# LeafCanV001.net
KiCad netlist of a schematic drawn in EAGLE
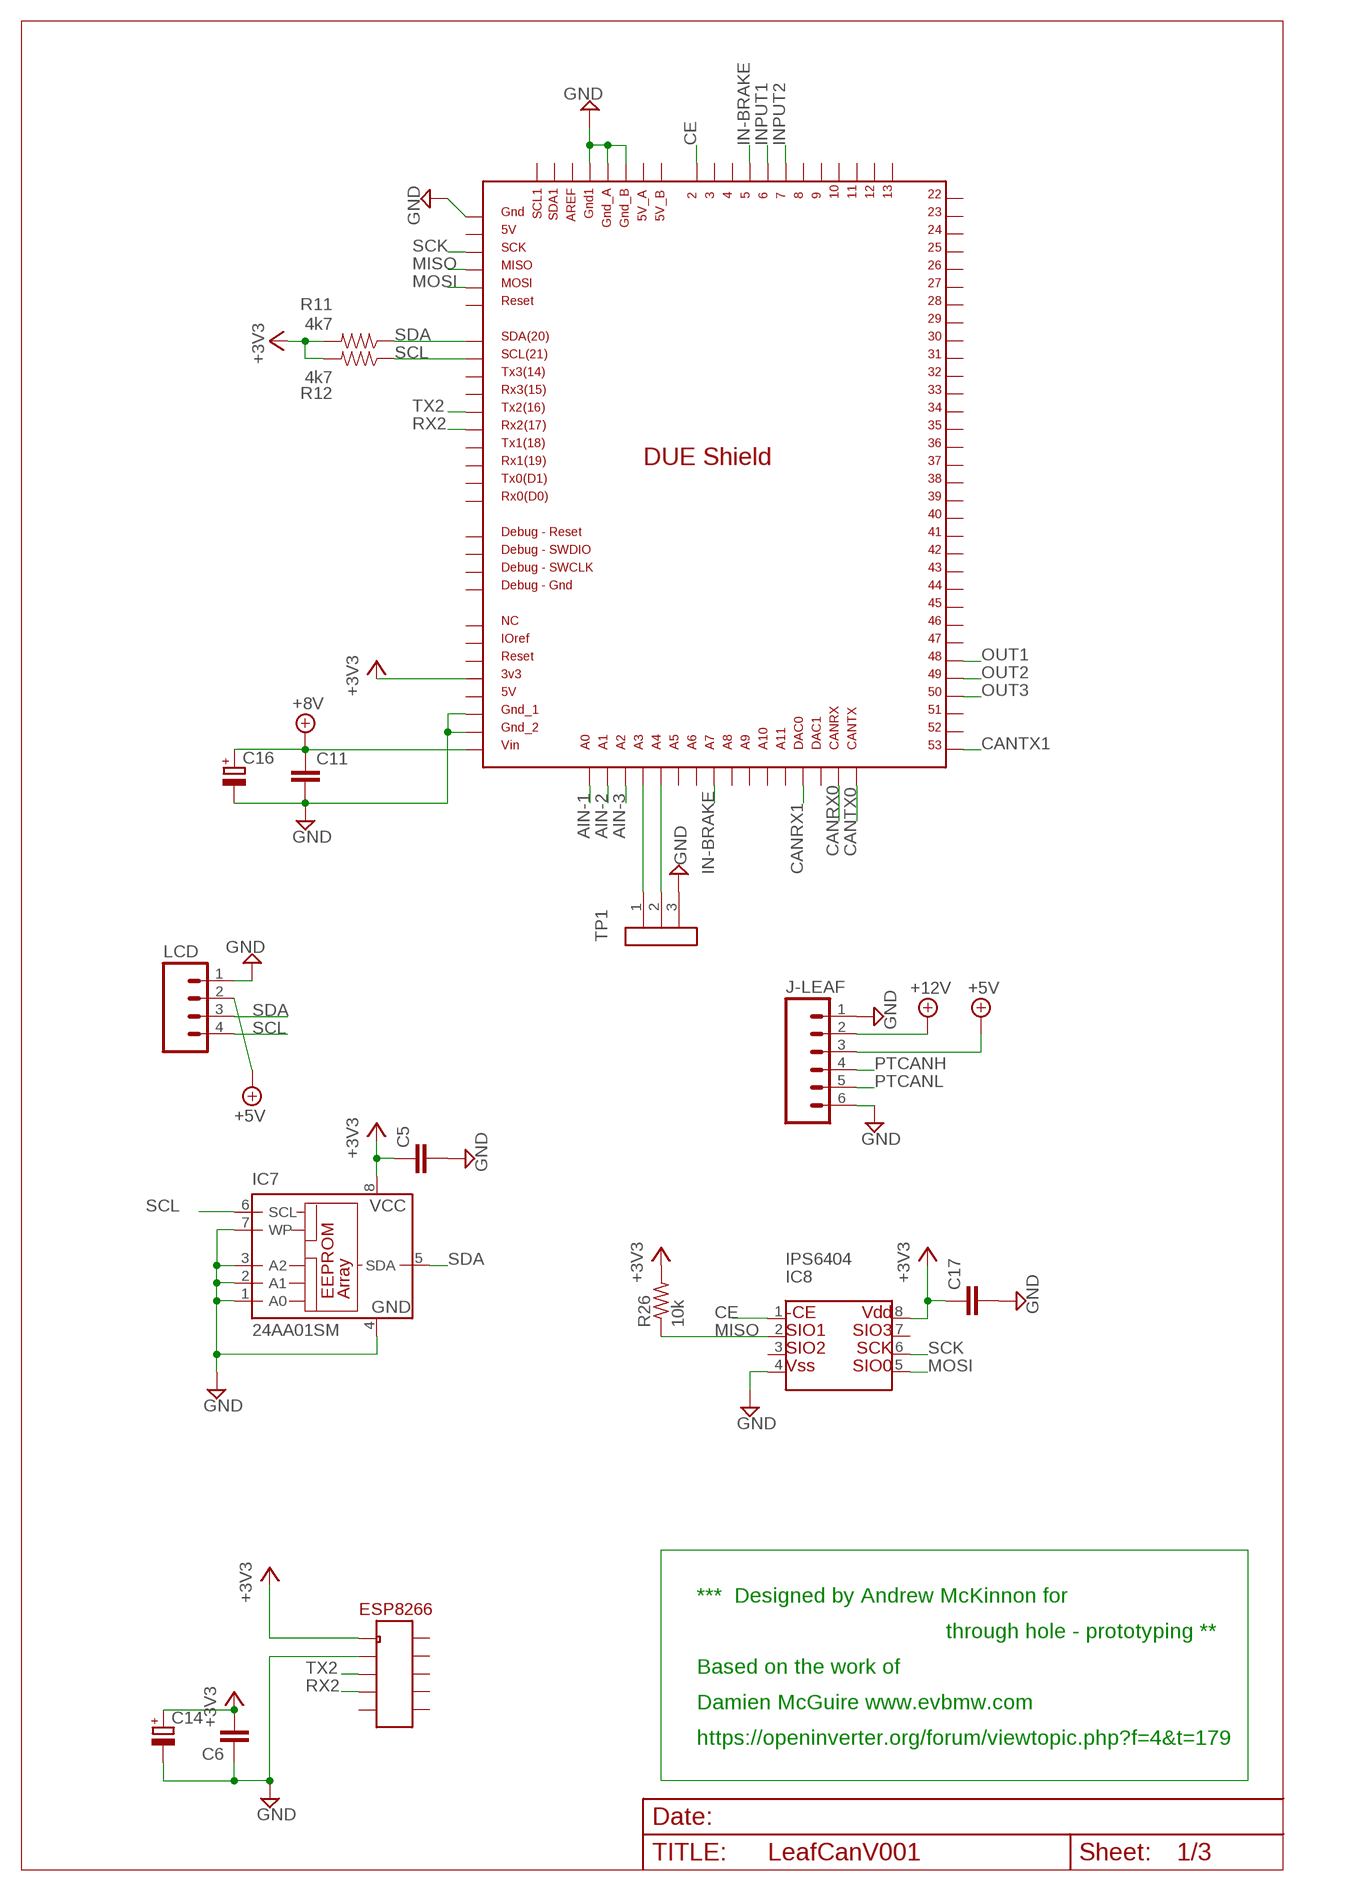
[diagram p0: schematic, sheet 1]
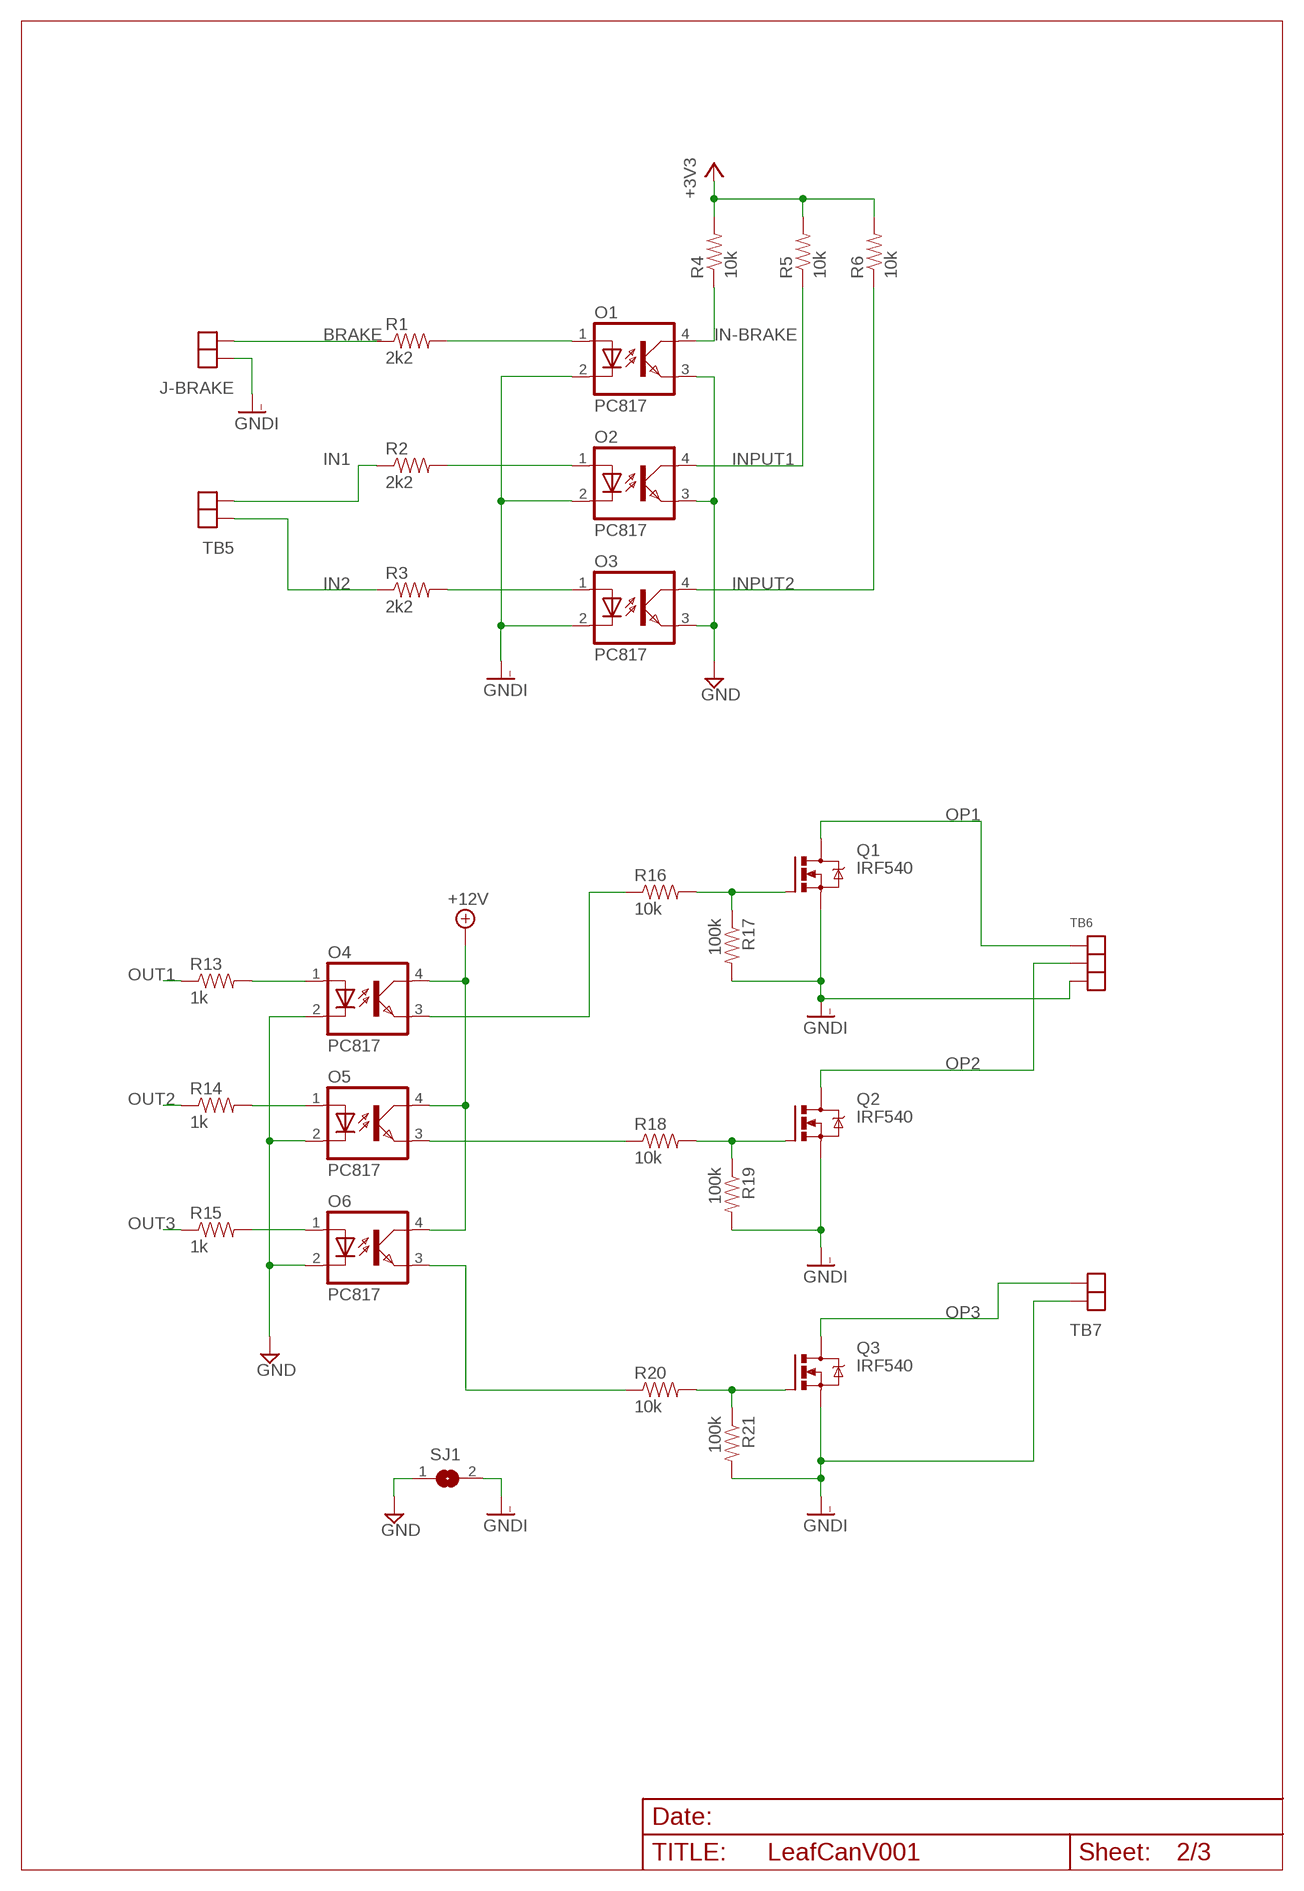
[diagram p1: schematic, sheet 2]
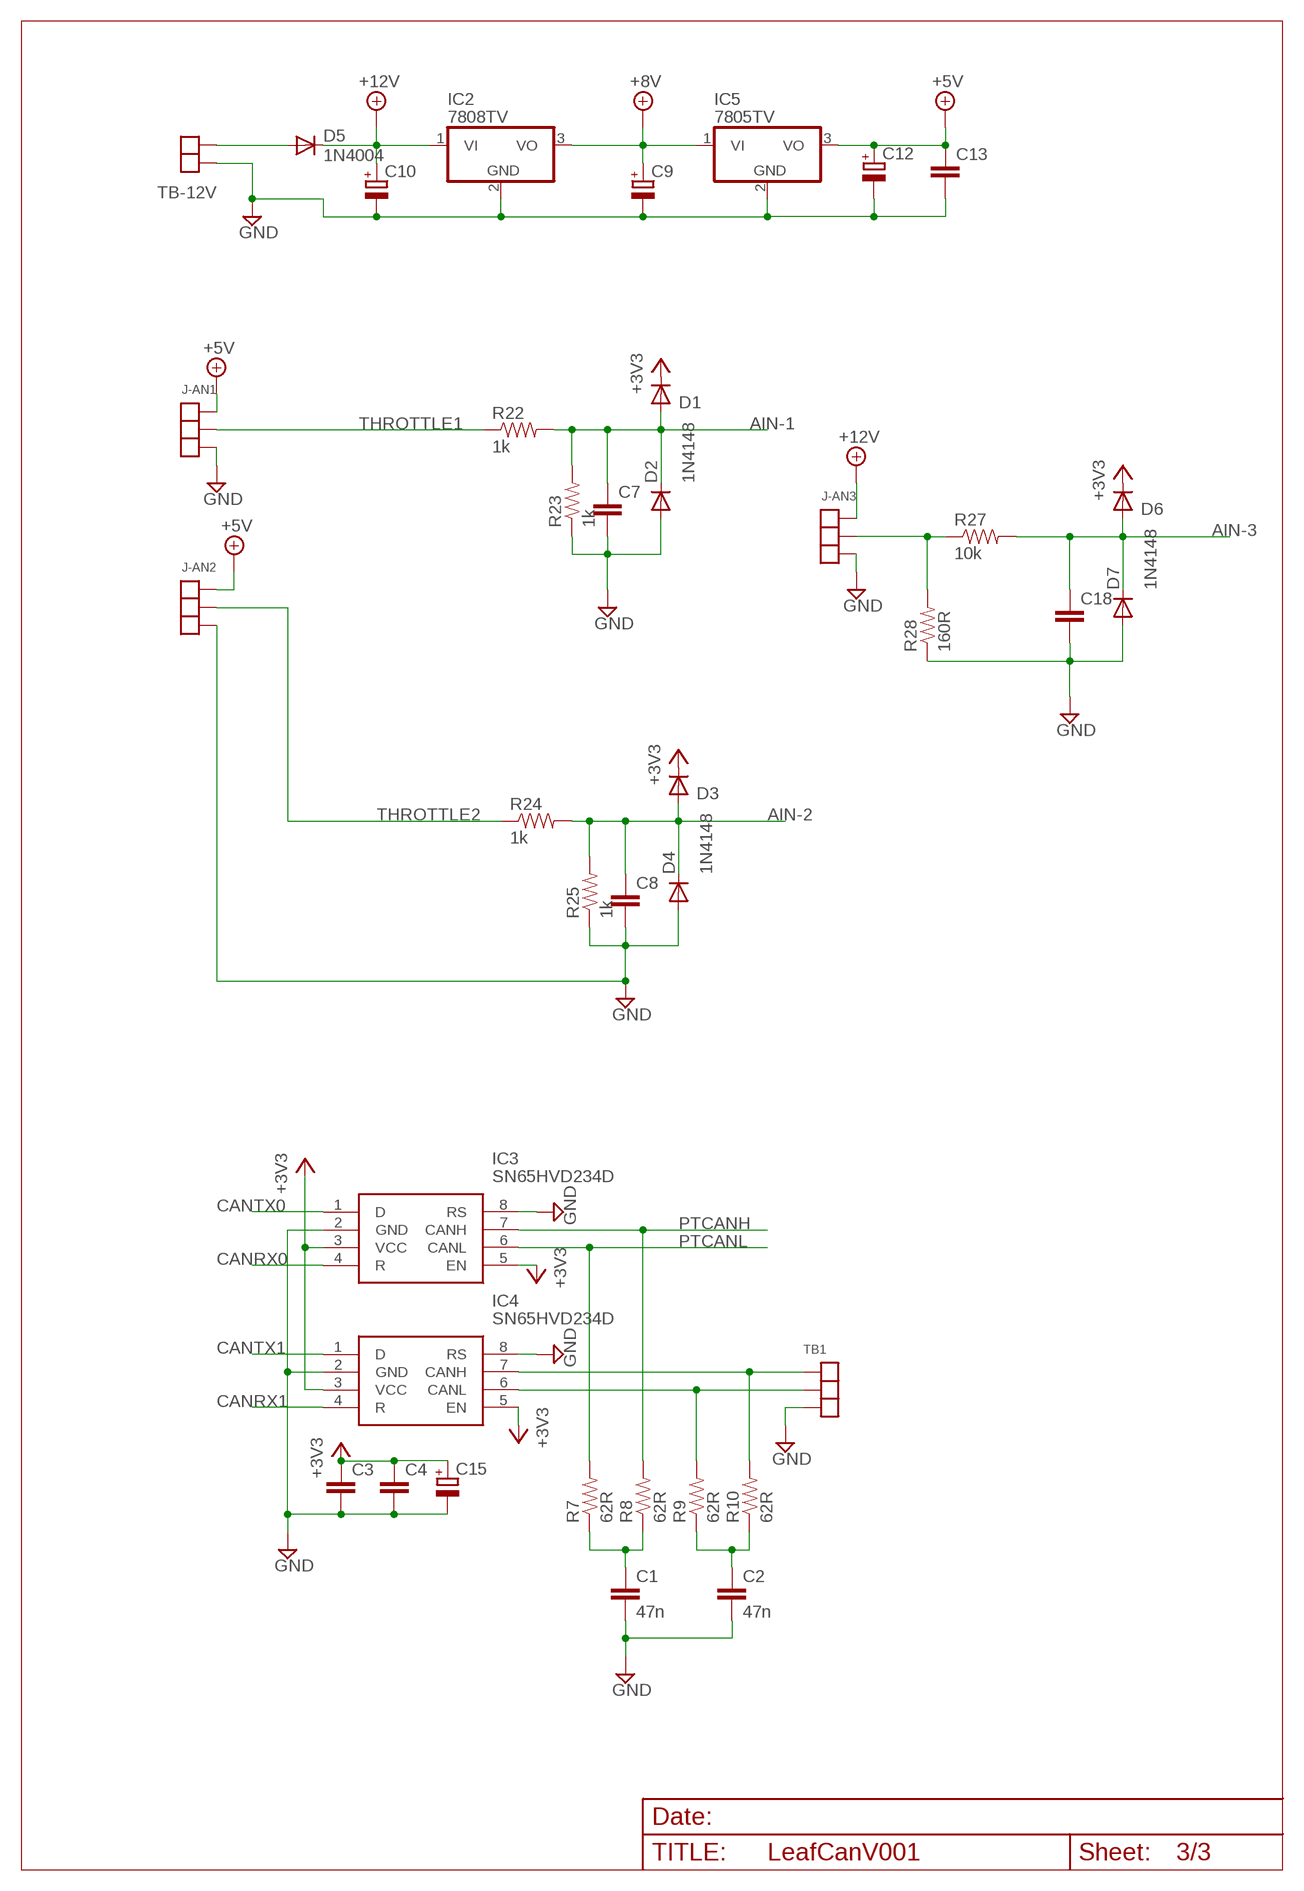
[diagram p2: schematic, sheet 3]

(export (version "E")
  (design (tool "Eeschema 10.0.6"))
  (components
    (comp (ref "C1")
      (value "47n")
      (footprint "eagle-import:C025-030X050")
      (libsource (lib "eagle-import") (part "C-EU025-030X050"))
    )
    (comp (ref "C2")
      (value "47n")
      (footprint "eagle-import:C025-030X050")
      (libsource (lib "eagle-import") (part "C-EU025-030X050"))
    )
    (comp (ref "C3")
      (value "BCAP")
      (footprint "eagle-import:BCAP")
      (libsource (lib "eagle-import") (part "BCAP"))
    )
    (comp (ref "C4")
      (value "BCAP")
      (footprint "eagle-import:BCAP")
      (libsource (lib "eagle-import") (part "BCAP"))
    )
    (comp (ref "C7")
      (value "BCAP")
      (footprint "eagle-import:BCAP")
      (libsource (lib "eagle-import") (part "BCAP"))
    )
    (comp (ref "C8")
      (value "BCAP")
      (footprint "eagle-import:BCAP")
      (libsource (lib "eagle-import") (part "BCAP"))
    )
    (comp (ref "C9")
      (value "C-RB200100")
      (footprint "eagle-import:CPOL-RADIAL-10UF-25V")
      (libsource (lib "eagle-import") (part "C-RB200100"))
    )
    (comp (ref "C10")
      (value "CPOL-EUE7.5-18")
      (footprint "eagle-import:E7,5-18")
      (libsource (lib "eagle-import") (part "CPOL-EUE7.5-18"))
    )
    (comp (ref "C12")
      (value "C-RB200100")
      (footprint "eagle-import:CPOL-RADIAL-10UF-25V")
      (libsource (lib "eagle-import") (part "C-RB200100"))
    )
    (comp (ref "C13")
      (value "BCAP")
      (footprint "eagle-import:BCAP")
      (libsource (lib "eagle-import") (part "BCAP"))
    )
    (comp (ref "C15")
      (value "C-RB200100")
      (footprint "eagle-import:CPOL-RADIAL-10UF-25V")
      (libsource (lib "eagle-import") (part "Andrew Passive_C-RB200100"))
    )
    (comp (ref "C18")
      (value "BCAP")
      (footprint "eagle-import:BCAP")
      (libsource (lib "eagle-import") (part "BCAP"))
    )
    (comp (ref "D1")
      (value "1N4148")
      (footprint "eagle-import:D3")
      (libsource (lib "eagle-import") (part "1N4148DO35-7"))
    )
    (comp (ref "D2")
      (value "1N4148")
      (footprint "eagle-import:D3")
      (libsource (lib "eagle-import") (part "1N4148DO35-7"))
    )
    (comp (ref "D3")
      (value "1N4148")
      (footprint "eagle-import:D3")
      (libsource (lib "eagle-import") (part "1N4148DO35-7"))
    )
    (comp (ref "D4")
      (value "1N4148")
      (footprint "eagle-import:D3")
      (libsource (lib "eagle-import") (part "1N4148DO35-7"))
    )
    (comp (ref "D5")
      (value "1N4004")
      (footprint "eagle-import:DO41-10")
      (libsource (lib "eagle-import") (part "1N4004"))
    )
    (comp (ref "D6")
      (value "1N4148")
      (footprint "eagle-import:D3")
      (libsource (lib "eagle-import") (part "1N4148DO35-7"))
    )
    (comp (ref "D7")
      (value "1N4148")
      (footprint "eagle-import:D3")
      (libsource (lib "eagle-import") (part "1N4148DO35-7"))
    )
    (comp (ref "IC2")
      (value "7808TV")
      (footprint "eagle-import:TO220V")
      (libsource (lib "eagle-import") (part "78TV08"))
    )
    (comp (ref "IC3")
      (value "SN65HVD234D")
      (footprint "eagle-import:SOIC127P600X175-8N")
      (fields
        (field (name "MOUSER_PART_NUMBER") "595-SN65HVD234D")
        (field (name "RS_PART_NUMBER") "6624315P")
      )
      (libsource (lib "eagle-import") (part "SN65HVD234D"))
    )
    (comp (ref "IC4")
      (value "SN65HVD234D")
      (footprint "eagle-import:SOIC127P600X175-8N")
      (fields
        (field (name "MOUSER_PART_NUMBER") "595-SN65HVD234D")
        (field (name "RS_PART_NUMBER") "6624315P")
      )
      (libsource (lib "eagle-import") (part "SN65HVD234D"))
    )
    (comp (ref "IC5")
      (value "7805TV")
      (footprint "eagle-import:TO220V")
      (libsource (lib "eagle-import") (part "78TV05"))
    )
    (comp (ref "J-AN1")
      (value "TB3381V")
      (footprint "eagle-import:TB-KF2EDG381-3-V")
      (libsource (lib "eagle-import") (part "TB3381V"))
    )
    (comp (ref "J-AN2")
      (value "TB3381V")
      (footprint "eagle-import:TB-KF2EDG381-3-V")
      (libsource (lib "eagle-import") (part "TB3381V"))
    )
    (comp (ref "J-AN3")
      (value "TB3381V")
      (footprint "eagle-import:TB-KF2EDG381-3-V")
      (libsource (lib "eagle-import") (part "TB3381V"))
    )
    (comp (ref "R7")
      (value "62R")
      (footprint "eagle-import:AXIAL-0.4")
      (libsource (lib "eagle-import") (part "R4"))
    )
    (comp (ref "R8")
      (value "62R")
      (footprint "eagle-import:AXIAL-0.4")
      (libsource (lib "eagle-import") (part "R4"))
    )
    (comp (ref "R9")
      (value "62R")
      (footprint "eagle-import:AXIAL-0.4")
      (libsource (lib "eagle-import") (part "R4"))
    )
    (comp (ref "R10")
      (value "62R")
      (footprint "eagle-import:AXIAL-0.4")
      (libsource (lib "eagle-import") (part "R4"))
    )
    (comp (ref "R22")
      (value "1k")
      (footprint "eagle-import:AXIAL-0.4")
      (libsource (lib "eagle-import") (part "R4"))
    )
    (comp (ref "R23")
      (value "1k")
      (footprint "eagle-import:AXIAL-0.4")
      (libsource (lib "eagle-import") (part "R4"))
    )
    (comp (ref "R24")
      (value "1k")
      (footprint "eagle-import:AXIAL-0.4")
      (libsource (lib "eagle-import") (part "R4"))
    )
    (comp (ref "R25")
      (value "1k")
      (footprint "eagle-import:AXIAL-0.4")
      (libsource (lib "eagle-import") (part "R4"))
    )
    (comp (ref "R27")
      (value "10k")
      (footprint "eagle-import:AXIAL-0.4")
      (libsource (lib "eagle-import") (part "R4"))
    )
    (comp (ref "R28")
      (value "160R")
      (footprint "eagle-import:AXIAL-0.4")
      (libsource (lib "eagle-import") (part "R4"))
    )
    (comp (ref "TB-12V")
      (value "TB2381")
      (footprint "eagle-import:TB-KF2EDG381-2P")
      (libsource (lib "eagle-import") (part "TB2381"))
    )
    (comp (ref "TB1")
      (value "TB3381V")
      (footprint "eagle-import:TB-KF2EDG381-3-V")
      (libsource (lib "eagle-import") (part "TB3381V"))
    )
    (comp (ref "J-BRAKE")
      (value "TB2381")
      (footprint "eagle-import:TB-KF2EDG381-2P")
      (libsource (lib "eagle-import") (part "TB2381"))
    )
    (comp (ref "O1")
      (value "PC817")
      (footprint "eagle-import:DIL04")
      (fields (field (name "MPN") "PC817X4J000F"))
      (libsource (lib "eagle-import") (part "PC817"))
    )
    (comp (ref "O2")
      (value "PC817")
      (footprint "eagle-import:DIL04")
      (fields (field (name "MPN") "PC817X4J000F"))
      (libsource (lib "eagle-import") (part "PC817"))
    )
    (comp (ref "O3")
      (value "PC817")
      (footprint "eagle-import:DIL04")
      (fields (field (name "MPN") "PC817X4J000F"))
      (libsource (lib "eagle-import") (part "PC817"))
    )
    (comp (ref "O4")
      (value "PC817")
      (footprint "eagle-import:DIL04")
      (fields (field (name "MPN") "PC817X4J000F"))
      (libsource (lib "eagle-import") (part "PC817"))
    )
    (comp (ref "O5")
      (value "PC817")
      (footprint "eagle-import:DIL04")
      (fields (field (name "MPN") "PC817X4J000F"))
      (libsource (lib "eagle-import") (part "PC817"))
    )
    (comp (ref "O6")
      (value "PC817")
      (footprint "eagle-import:DIL04")
      (fields (field (name "MPN") "PC817X4J000F"))
      (libsource (lib "eagle-import") (part "PC817"))
    )
    (comp (ref "Q1")
      (value "IRF540")
      (footprint "eagle-import:TO220BV")
      (libsource (lib "eagle-import") (part "IRF540"))
    )
    (comp (ref "Q2")
      (value "IRF540")
      (footprint "eagle-import:TO220BV")
      (libsource (lib "eagle-import") (part "IRF540"))
    )
    (comp (ref "Q3")
      (value "IRF540")
      (footprint "eagle-import:TO220BV")
      (libsource (lib "eagle-import") (part "IRF540"))
    )
    (comp (ref "R1")
      (value "2k2")
      (footprint "eagle-import:AXIAL-0.4")
      (libsource (lib "eagle-import") (part "R4"))
    )
    (comp (ref "R2")
      (value "2k2")
      (footprint "eagle-import:AXIAL-0.4")
      (libsource (lib "eagle-import") (part "R4"))
    )
    (comp (ref "R3")
      (value "2k2")
      (footprint "eagle-import:AXIAL-0.4")
      (libsource (lib "eagle-import") (part "R4"))
    )
    (comp (ref "R4")
      (value "10k")
      (footprint "eagle-import:AXIAL-0.4")
      (libsource (lib "eagle-import") (part "R4"))
    )
    (comp (ref "R5")
      (value "10k")
      (footprint "eagle-import:AXIAL-0.4")
      (libsource (lib "eagle-import") (part "R4"))
    )
    (comp (ref "R6")
      (value "10k")
      (footprint "eagle-import:AXIAL-0.4")
      (libsource (lib "eagle-import") (part "R4"))
    )
    (comp (ref "R13")
      (value "1k")
      (footprint "eagle-import:AXIAL-0.4")
      (libsource (lib "eagle-import") (part "R4"))
    )
    (comp (ref "R14")
      (value "1k")
      (footprint "eagle-import:AXIAL-0.4")
      (libsource (lib "eagle-import") (part "R4"))
    )
    (comp (ref "R15")
      (value "1k")
      (footprint "eagle-import:AXIAL-0.4")
      (libsource (lib "eagle-import") (part "R4"))
    )
    (comp (ref "R16")
      (value "10k")
      (footprint "eagle-import:AXIAL-0.4")
      (libsource (lib "eagle-import") (part "R4"))
    )
    (comp (ref "R17")
      (value "100k")
      (footprint "eagle-import:AXIAL-0.4")
      (libsource (lib "eagle-import") (part "R4"))
    )
    (comp (ref "R18")
      (value "10k")
      (footprint "eagle-import:AXIAL-0.4")
      (libsource (lib "eagle-import") (part "R4"))
    )
    (comp (ref "R19")
      (value "100k")
      (footprint "eagle-import:AXIAL-0.4")
      (libsource (lib "eagle-import") (part "R4"))
    )
    (comp (ref "R20")
      (value "10k")
      (footprint "eagle-import:AXIAL-0.4")
      (libsource (lib "eagle-import") (part "R4"))
    )
    (comp (ref "R21")
      (value "100k")
      (footprint "eagle-import:AXIAL-0.4")
      (libsource (lib "eagle-import") (part "R4"))
    )
    (comp (ref "SJ1") (value "SJ") (footprint "eagle-import:SJ") (libsource (lib "eagle-import") (part "SJ")))
    (comp (ref "TB5")
      (value "TB2381")
      (footprint "eagle-import:TB-KF2EDG381-2P")
      (libsource (lib "eagle-import") (part "TB2381"))
    )
    (comp (ref "TB6")
      (value "TB3381")
      (footprint "eagle-import:TB-KF2EDG381-3P")
      (libsource (lib "eagle-import") (part "TB3381"))
    )
    (comp (ref "TB7")
      (value "TB2381")
      (footprint "eagle-import:TB-KF2EDG381-2P")
      (libsource (lib "eagle-import") (part "TB2381"))
    )
    (comp (ref "C5")
      (value "BCAP")
      (footprint "eagle-import:BCAP")
      (libsource (lib "eagle-import") (part "BCAP"))
    )
    (comp (ref "C6")
      (value "BCAP")
      (footprint "eagle-import:BCAP")
      (libsource (lib "eagle-import") (part "BCAP"))
    )
    (comp (ref "C11")
      (value "BCAP")
      (footprint "eagle-import:BCAP")
      (libsource (lib "eagle-import") (part "BCAP"))
    )
    (comp (ref "C14")
      (value "C-RB200100")
      (footprint "eagle-import:CPOL-RADIAL-10UF-25V")
      (libsource (lib "eagle-import") (part "Andrew Passive_C-RB200100"))
    )
    (comp (ref "C16")
      (value "C-RB200100")
      (footprint "eagle-import:CPOL-RADIAL-10UF-25V")
      (libsource (lib "eagle-import") (part "Andrew Passive_C-RB200100"))
    )
    (comp (ref "C17")
      (value "BCAP")
      (footprint "eagle-import:BCAP")
      (libsource (lib "eagle-import") (part "BCAP"))
    )
    (comp (ref "ESP8266")
      (value "IDC10")
      (footprint "eagle-import:IDC10-SMALL")
      (libsource (lib "eagle-import") (part "IDC10"))
    )
    (comp (ref "IC1")
      (value "DUE(NORMAL)")
      (footprint "eagle-import:DUE(NORMAL)")
      (libsource (lib "eagle-import") (part "DUE(NORMAL)"))
    )
    (comp (ref "IC7")
      (value "24AA01SM")
      (footprint "eagle-import:SO-08M")
      (fields (field (name "MF") "MICROCHIP") (field (name "MPN") "24AA01-I/SN"))
      (libsource (lib "eagle-import") (part "24SMAA01"))
    )
    (comp (ref "IC8")
      (value "IPS6404")
      (footprint "eagle-import:SO-08")
      (libsource (lib "eagle-import") (part "IPS6404"))
    )
    (comp (ref "J-LEAF")
      (value "MO6POL")
      (footprint "eagle-import:MOLEX-6")
      (libsource (lib "eagle-import") (part "MO6POL"))
    )
    (comp (ref "LCD")
      (value "MO4POL")
      (footprint "eagle-import:MOLEX-4")
      (libsource (lib "eagle-import") (part "MO4POL"))
    )
    (comp (ref "R11")
      (value "4k7")
      (footprint "eagle-import:AXIAL-0.4")
      (libsource (lib "eagle-import") (part "R4"))
    )
    (comp (ref "R12")
      (value "4k7")
      (footprint "eagle-import:AXIAL-0.4")
      (libsource (lib "eagle-import") (part "R4"))
    )
    (comp (ref "R26")
      (value "10k")
      (footprint "eagle-import:R1206")
      (libsource (lib "eagle-import") (part "R-US_R1206"))
    )
    (comp (ref "TP1")
      (value "SIL3")
      (footprint "eagle-import:SIL3")
      (libsource (lib "eagle-import") (part "SIL3"))
    )
  )
  (nets
    (net (code "1") (name "+3V3") (class "Default")
      (node (ref "C14") (pin "1") (pinfunction "+_1") (pintype "passive"))
      (node (ref "C15") (pin "1") (pinfunction "+_1") (pintype "passive"))
      (node (ref "C17") (pin "1") (pinfunction "1_1") (pintype "passive"))
      (node (ref "C3") (pin "1") (pinfunction "1_1") (pintype "passive"))
      (node (ref "C4") (pin "1") (pinfunction "1_1") (pintype "passive"))
      (node (ref "C5") (pin "1") (pinfunction "1_1") (pintype "passive"))
      (node (ref "C6") (pin "2") (pinfunction "2_2") (pintype "passive"))
      (node (ref "D1") (pin "C") (pinfunction "C_C") (pintype "passive"))
      (node (ref "D3") (pin "C") (pinfunction "C_C") (pintype "passive"))
      (node (ref "D6") (pin "C") (pinfunction "C_C") (pintype "passive"))
      (node (ref "ESP8266") (pin "1") (pinfunction "1_1") (pintype "bidirectional"))
      (node (ref "IC1") (pin "3V3") (pinfunction "3V3_3V3") (pintype "bidirectional"))
      (node (ref "IC3") (pin "3") (pinfunction "VCC_3") (pintype "bidirectional"))
      (node (ref "IC3") (pin "5") (pinfunction "EN_5") (pintype "bidirectional"))
      (node (ref "IC4") (pin "3") (pinfunction "VCC_3") (pintype "bidirectional"))
      (node (ref "IC4") (pin "5") (pinfunction "EN_5") (pintype "bidirectional"))
      (node (ref "IC7") (pin "8") (pinfunction "VCC_8") (pintype "power_in"))
      (node (ref "IC8") (pin "8") (pinfunction "P$8_8") (pintype "bidirectional"))
      (node (ref "R11") (pin "P$2") (pinfunction "2_P$2") (pintype "passive"))
      (node (ref "R12") (pin "P$2") (pinfunction "2_P$2") (pintype "passive"))
      (node (ref "R26") (pin "2") (pinfunction "2_2") (pintype "passive"))
      (node (ref "R4") (pin "P$2") (pinfunction "2_P$2") (pintype "passive"))
      (node (ref "R5") (pin "P$2") (pinfunction "2_P$2") (pintype "passive"))
      (node (ref "R6") (pin "P$2") (pinfunction "2_P$2") (pintype "passive"))
    )
    (net (code "2") (name "+5V") (class "Default")
      (node (ref "C12") (pin "1") (pinfunction "+_1") (pintype "passive"))
      (node (ref "C13") (pin "1") (pinfunction "1_1") (pintype "passive"))
      (node (ref "IC5") (pin "3") (pinfunction "VO_3") (pintype "passive"))
      (node (ref "J-AN1") (pin "1") (pinfunction "1_1") (pintype "bidirectional"))
      (node (ref "J-AN2") (pin "1") (pinfunction "1_1") (pintype "bidirectional"))
      (node (ref "J-LEAF") (pin "3") (pinfunction "3_3") (pintype "passive"))
      (node (ref "LCD") (pin "2") (pinfunction "2_2") (pintype "passive"))
    )
    (net (code "3") (name "+8V") (class "Default")
      (node (ref "C11") (pin "1") (pinfunction "1_1") (pintype "passive"))
      (node (ref "C16") (pin "1") (pinfunction "+_1") (pintype "passive"))
      (node (ref "C9") (pin "1") (pinfunction "+_1") (pintype "passive"))
      (node (ref "IC1") (pin "VIN") (pinfunction "VIN_VIN") (pintype "bidirectional"))
      (node (ref "IC2") (pin "3") (pinfunction "VO_3") (pintype "passive"))
      (node (ref "IC5") (pin "1") (pinfunction "VI_1") (pintype "input"))
    )
    (net (code "4") (name "+12V") (class "Default")
      (node (ref "C10") (pin "+") (pinfunction "+_+") (pintype "passive"))
      (node (ref "D5") (pin "C") (pinfunction "C_C") (pintype "passive"))
      (node (ref "IC2") (pin "1") (pinfunction "VI_1") (pintype "input"))
      (node (ref "J-AN3") (pin "1") (pinfunction "1_1") (pintype "bidirectional"))
      (node (ref "J-LEAF") (pin "2") (pinfunction "2_2") (pintype "passive"))
      (node (ref "O4") (pin "4") (pinfunction "COL_4") (pintype "passive"))
      (node (ref "O5") (pin "4") (pinfunction "COL_4") (pintype "passive"))
      (node (ref "O6") (pin "4") (pinfunction "COL_4") (pintype "passive"))
    )
    (net (code "5") (name "AIN-1") (class "Default")
      (node (ref "C7") (pin "1") (pinfunction "1_1") (pintype "passive"))
      (node (ref "D1") (pin "A") (pinfunction "A_A") (pintype "passive"))
      (node (ref "D2") (pin "C") (pinfunction "C_C") (pintype "passive"))
      (node (ref "IC1") (pin "A0") (pinfunction "A0_A0") (pintype "bidirectional"))
      (node (ref "R22") (pin "P$2") (pinfunction "2_P$2") (pintype "passive"))
      (node (ref "R23") (pin "P$2") (pinfunction "2_P$2") (pintype "passive"))
    )
    (net (code "6") (name "AIN-2") (class "Default")
      (node (ref "C8") (pin "1") (pinfunction "1_1") (pintype "passive"))
      (node (ref "D3") (pin "A") (pinfunction "A_A") (pintype "passive"))
      (node (ref "D4") (pin "C") (pinfunction "C_C") (pintype "passive"))
      (node (ref "IC1") (pin "A1") (pinfunction "A1_A1") (pintype "bidirectional"))
      (node (ref "R24") (pin "P$2") (pinfunction "2_P$2") (pintype "passive"))
      (node (ref "R25") (pin "P$2") (pinfunction "2_P$2") (pintype "passive"))
    )
    (net (code "7") (name "AIN-3") (class "Default")
      (node (ref "C18") (pin "1") (pinfunction "1_1") (pintype "passive"))
      (node (ref "D6") (pin "A") (pinfunction "A_A") (pintype "passive"))
      (node (ref "D7") (pin "C") (pinfunction "C_C") (pintype "passive"))
      (node (ref "IC1") (pin "A2") (pinfunction "A2_A2") (pintype "bidirectional"))
      (node (ref "R27") (pin "P$2") (pinfunction "2_P$2") (pintype "passive"))
    )
    (net (code "8") (name "BRAKE") (class "Default")
      (node (ref "J-BRAKE") (pin "1") (pinfunction "1_1") (pintype "bidirectional"))
      (node (ref "R1") (pin "P$1") (pinfunction "1_P$1") (pintype "passive"))
    )
    (net (code "9") (name "CANRX0") (class "Default")
      (node (ref "IC1") (pin "CANRX") (pinfunction "CANRX_CANRX") (pintype "bidirectional"))
      (node (ref "IC3") (pin "4") (pinfunction "R_4") (pintype "bidirectional"))
    )
    (net (code "10") (name "CANRX1") (class "Default")
      (node (ref "IC1") (pin "DAC0") (pinfunction "DAC0_DAC0") (pintype "bidirectional"))
      (node (ref "IC4") (pin "4") (pinfunction "R_4") (pintype "bidirectional"))
    )
    (net (code "11") (name "CANTX0") (class "Default")
      (node (ref "IC1") (pin "CANTX") (pinfunction "CANTX_CANTX") (pintype "bidirectional"))
      (node (ref "IC3") (pin "1") (pinfunction "D_1") (pintype "bidirectional"))
    )
    (net (code "12") (name "CANTX1") (class "Default")
      (node (ref "IC1") (pin "53") (pinfunction "53_53") (pintype "bidirectional"))
      (node (ref "IC4") (pin "1") (pinfunction "D_1") (pintype "bidirectional"))
    )
    (net (code "13") (name "CE") (class "Default")
      (node (ref "IC1") (pin "2") (pinfunction "2_2") (pintype "bidirectional"))
      (node (ref "IC8") (pin "1") (pinfunction "P$1_1") (pintype "bidirectional"))
    )
    (net (code "14") (name "GND") (class "Default")
      (node (ref "C1") (pin "2") (pinfunction "2_2") (pintype "passive"))
      (node (ref "C10") (pin "-") (pinfunction "-_-") (pintype "passive"))
      (node (ref "C11") (pin "2") (pinfunction "2_2") (pintype "passive"))
      (node (ref "C12") (pin "2") (pinfunction "-_2") (pintype "passive"))
      (node (ref "C13") (pin "2") (pinfunction "2_2") (pintype "passive"))
      (node (ref "C14") (pin "2") (pinfunction "-_2") (pintype "passive"))
      (node (ref "C15") (pin "2") (pinfunction "-_2") (pintype "passive"))
      (node (ref "C16") (pin "2") (pinfunction "-_2") (pintype "passive"))
      (node (ref "C17") (pin "2") (pinfunction "2_2") (pintype "passive"))
      (node (ref "C18") (pin "2") (pinfunction "2_2") (pintype "passive"))
      (node (ref "C2") (pin "2") (pinfunction "2_2") (pintype "passive"))
      (node (ref "C3") (pin "2") (pinfunction "2_2") (pintype "passive"))
      (node (ref "C4") (pin "2") (pinfunction "2_2") (pintype "passive"))
      (node (ref "C5") (pin "2") (pinfunction "2_2") (pintype "passive"))
      (node (ref "C6") (pin "1") (pinfunction "1_1") (pintype "passive"))
      (node (ref "C7") (pin "2") (pinfunction "2_2") (pintype "passive"))
      (node (ref "C8") (pin "2") (pinfunction "2_2") (pintype "passive"))
      (node (ref "C9") (pin "2") (pinfunction "-_2") (pintype "passive"))
      (node (ref "D2") (pin "A") (pinfunction "A_A") (pintype "passive"))
      (node (ref "D4") (pin "A") (pinfunction "A_A") (pintype "passive"))
      (node (ref "D7") (pin "A") (pinfunction "A_A") (pintype "passive"))
      (node (ref "ESP8266") (pin "3") (pinfunction "3_3") (pintype "bidirectional"))
      (node (ref "IC1") (pin "5V_ICSP") (pinfunction "5V_ICSP_5V_ICSP") (pintype "bidirectional"))
      (node (ref "IC1") (pin "GND1") (pinfunction "GND1_GND1") (pintype "bidirectional"))
      (node (ref "IC1") (pin "GND_1") (pinfunction "GND_1_GND_1") (pintype "bidirectional"))
      (node (ref "IC1") (pin "GND_2") (pinfunction "GND_2_GND_2") (pintype "bidirectional"))
      (node (ref "IC1") (pin "GND_A") (pinfunction "GND_A_GND_A") (pintype "bidirectional"))
      (node (ref "IC1") (pin "GND_B") (pinfunction "GND_B_GND_B") (pintype "bidirectional"))
      (node (ref "IC2") (pin "2") (pinfunction "GND_2") (pintype "passive"))
      (node (ref "IC3") (pin "2") (pinfunction "GND_2") (pintype "bidirectional"))
      (node (ref "IC3") (pin "8") (pinfunction "RS_8") (pintype "bidirectional"))
      (node (ref "IC4") (pin "2") (pinfunction "GND_2") (pintype "bidirectional"))
      (node (ref "IC4") (pin "8") (pinfunction "RS_8") (pintype "bidirectional"))
      (node (ref "IC5") (pin "2") (pinfunction "GND_2") (pintype "passive"))
      (node (ref "IC7") (pin "1") (pinfunction "A0_1") (pintype "input"))
      (node (ref "IC7") (pin "2") (pinfunction "A1_2") (pintype "input"))
      (node (ref "IC7") (pin "3") (pinfunction "A2_3") (pintype "input"))
      (node (ref "IC7") (pin "4") (pinfunction "GND_4") (pintype "power_in"))
      (node (ref "IC7") (pin "7") (pinfunction "WP_7") (pintype "input"))
      (node (ref "IC8") (pin "4") (pinfunction "P$4_4") (pintype "bidirectional"))
      (node (ref "J-AN1") (pin "3") (pinfunction "3_3") (pintype "bidirectional"))
      (node (ref "J-AN2") (pin "3") (pinfunction "3_3") (pintype "bidirectional"))
      (node (ref "J-AN3") (pin "3") (pinfunction "3_3") (pintype "bidirectional"))
      (node (ref "J-LEAF") (pin "1") (pinfunction "1_1") (pintype "passive"))
      (node (ref "J-LEAF") (pin "6") (pinfunction "6_6") (pintype "passive"))
      (node (ref "LCD") (pin "1") (pinfunction "1_1") (pintype "passive"))
      (node (ref "O1") (pin "3") (pinfunction "EMIT_3") (pintype "passive"))
      (node (ref "O2") (pin "3") (pinfunction "EMIT_3") (pintype "passive"))
      (node (ref "O3") (pin "3") (pinfunction "EMIT_3") (pintype "passive"))
      (node (ref "O4") (pin "2") (pinfunction "C_2") (pintype "passive"))
      (node (ref "O5") (pin "2") (pinfunction "C_2") (pintype "passive"))
      (node (ref "O6") (pin "2") (pinfunction "C_2") (pintype "passive"))
      (node (ref "R23") (pin "P$1") (pinfunction "1_P$1") (pintype "passive"))
      (node (ref "R25") (pin "P$1") (pinfunction "1_P$1") (pintype "passive"))
      (node (ref "R28") (pin "P$1") (pinfunction "1_P$1") (pintype "passive"))
      (node (ref "SJ1") (pin "1") (pinfunction "1_1") (pintype "passive"))
      (node (ref "TB-12V") (pin "2") (pinfunction "2_2") (pintype "bidirectional"))
      (node (ref "TB1") (pin "3") (pinfunction "3_3") (pintype "bidirectional"))
      (node (ref "TP1") (pin "3") (pinfunction "P$3_3") (pintype "bidirectional"))
    )
    (net (code "15") (name "GNDI") (class "Default")
      (node (ref "J-BRAKE") (pin "2") (pinfunction "2_2") (pintype "bidirectional"))
      (node (ref "O1") (pin "2") (pinfunction "C_2") (pintype "passive"))
      (node (ref "O2") (pin "2") (pinfunction "C_2") (pintype "passive"))
      (node (ref "O3") (pin "2") (pinfunction "C_2") (pintype "passive"))
      (node (ref "Q1") (pin "S") (pinfunction "S_S") (pintype "passive"))
      (node (ref "Q2") (pin "S") (pinfunction "S_S") (pintype "passive"))
      (node (ref "Q3") (pin "S") (pinfunction "S_S") (pintype "passive"))
      (node (ref "R17") (pin "P$2") (pinfunction "2_P$2") (pintype "passive"))
      (node (ref "R19") (pin "P$2") (pinfunction "2_P$2") (pintype "passive"))
      (node (ref "R21") (pin "P$2") (pinfunction "2_P$2") (pintype "passive"))
      (node (ref "SJ1") (pin "2") (pinfunction "2_2") (pintype "passive"))
      (node (ref "TB6") (pin "3") (pinfunction "3_3") (pintype "bidirectional"))
      (node (ref "TB7") (pin "2") (pinfunction "2_2") (pintype "bidirectional"))
    )
    (net (code "16") (name "IN-BRAKE") (class "Default")
      (node (ref "IC1") (pin "5") (pinfunction "5_5") (pintype "bidirectional"))
      (node (ref "IC1") (pin "A7") (pinfunction "A7_A7") (pintype "bidirectional"))
      (node (ref "O1") (pin "4") (pinfunction "COL_4") (pintype "passive"))
      (node (ref "R4") (pin "P$1") (pinfunction "1_P$1") (pintype "passive"))
    )
    (net (code "17") (name "IN1") (class "Default")
      (node (ref "R2") (pin "P$1") (pinfunction "1_P$1") (pintype "passive"))
      (node (ref "TB5") (pin "1") (pinfunction "1_1") (pintype "bidirectional"))
    )
    (net (code "18") (name "IN2") (class "Default")
      (node (ref "R3") (pin "P$1") (pinfunction "1_P$1") (pintype "passive"))
      (node (ref "TB5") (pin "2") (pinfunction "2_2") (pintype "bidirectional"))
    )
    (net (code "19") (name "INPUT1") (class "Default")
      (node (ref "IC1") (pin "6") (pinfunction "6_6") (pintype "bidirectional"))
      (node (ref "O2") (pin "4") (pinfunction "COL_4") (pintype "passive"))
      (node (ref "R5") (pin "P$1") (pinfunction "1_P$1") (pintype "passive"))
    )
    (net (code "20") (name "INPUT2") (class "Default")
      (node (ref "IC1") (pin "7") (pinfunction "7_7") (pintype "bidirectional"))
      (node (ref "O3") (pin "4") (pinfunction "COL_4") (pintype "passive"))
      (node (ref "R6") (pin "P$1") (pinfunction "1_P$1") (pintype "passive"))
    )
    (net (code "21") (name "MISO") (class "Default")
      (node (ref "IC1") (pin "MISO_ICSP") (pinfunction "MISO_ICSP_MISO_ICSP") (pintype "bidirectional"))
      (node (ref "IC8") (pin "2") (pinfunction "P$2_2") (pintype "bidirectional"))
      (node (ref "R26") (pin "1") (pinfunction "1_1") (pintype "passive"))
    )
    (net (code "22") (name "MOSI") (class "Default")
      (node (ref "IC1") (pin "MOSI_ICSP") (pinfunction "MOSI_ICSP_MOSI_ICSP") (pintype "bidirectional"))
      (node (ref "IC8") (pin "5") (pinfunction "P$5_5") (pintype "bidirectional"))
    )
    (net (code "23") (name "Net-(D5-PadA)") (class "Default")
      (node (ref "D5") (pin "A") (pinfunction "A_A") (pintype "passive"))
      (node (ref "TB-12V") (pin "1") (pinfunction "1_1") (pintype "bidirectional"))
    )
    (net (code "24") (name "Net-(IC4-CANH)") (class "Default")
      (node (ref "IC4") (pin "7") (pinfunction "CANH_7") (pintype "bidirectional"))
      (node (ref "R10") (pin "P$2") (pinfunction "2_P$2") (pintype "passive"))
      (node (ref "TB1") (pin "1") (pinfunction "1_1") (pintype "bidirectional"))
    )
    (net (code "25") (name "Net-(IC4-CANL)") (class "Default")
      (node (ref "IC4") (pin "6") (pinfunction "CANL_6") (pintype "bidirectional"))
      (node (ref "R9") (pin "P$2") (pinfunction "2_P$2") (pintype "passive"))
      (node (ref "TB1") (pin "2") (pinfunction "2_2") (pintype "bidirectional"))
    )
    (net (code "26") (name "Net-(O1-A)") (class "Default")
      (node (ref "O1") (pin "1") (pinfunction "A_1") (pintype "passive"))
      (node (ref "R1") (pin "P$2") (pinfunction "2_P$2") (pintype "passive"))
    )
    (net (code "27") (name "Net-(O2-A)") (class "Default")
      (node (ref "O2") (pin "1") (pinfunction "A_1") (pintype "passive"))
      (node (ref "R2") (pin "P$2") (pinfunction "2_P$2") (pintype "passive"))
    )
    (net (code "28") (name "Net-(O3-A)") (class "Default")
      (node (ref "O3") (pin "1") (pinfunction "A_1") (pintype "passive"))
      (node (ref "R3") (pin "P$2") (pinfunction "2_P$2") (pintype "passive"))
    )
    (net (code "29") (name "Net-(O4-A)") (class "Default")
      (node (ref "O4") (pin "1") (pinfunction "A_1") (pintype "passive"))
      (node (ref "R13") (pin "P$2") (pinfunction "2_P$2") (pintype "passive"))
    )
    (net (code "30") (name "Net-(O4-EMIT)") (class "Default")
      (node (ref "O4") (pin "3") (pinfunction "EMIT_3") (pintype "passive"))
      (node (ref "R16") (pin "P$1") (pinfunction "1_P$1") (pintype "passive"))
    )
    (net (code "31") (name "Net-(O5-A)") (class "Default")
      (node (ref "O5") (pin "1") (pinfunction "A_1") (pintype "passive"))
      (node (ref "R14") (pin "P$2") (pinfunction "2_P$2") (pintype "passive"))
    )
    (net (code "32") (name "Net-(O5-EMIT)") (class "Default")
      (node (ref "O5") (pin "3") (pinfunction "EMIT_3") (pintype "passive"))
      (node (ref "R18") (pin "P$1") (pinfunction "1_P$1") (pintype "passive"))
    )
    (net (code "33") (name "Net-(O6-A)") (class "Default")
      (node (ref "O6") (pin "1") (pinfunction "A_1") (pintype "passive"))
      (node (ref "R15") (pin "P$2") (pinfunction "2_P$2") (pintype "passive"))
    )
    (net (code "34") (name "Net-(O6-EMIT)") (class "Default")
      (node (ref "O6") (pin "3") (pinfunction "EMIT_3") (pintype "passive"))
      (node (ref "R20") (pin "P$1") (pinfunction "1_P$1") (pintype "passive"))
    )
    (net (code "35") (name "Net-(R7-1)") (class "Default")
      (node (ref "C1") (pin "1") (pinfunction "1_1") (pintype "passive"))
      (node (ref "R7") (pin "P$1") (pinfunction "1_P$1") (pintype "passive"))
      (node (ref "R8") (pin "P$1") (pinfunction "1_P$1") (pintype "passive"))
    )
    (net (code "36") (name "Net-(R10-1)") (class "Default")
      (node (ref "C2") (pin "1") (pinfunction "1_1") (pintype "passive"))
      (node (ref "R10") (pin "P$1") (pinfunction "1_P$1") (pintype "passive"))
      (node (ref "R9") (pin "P$1") (pinfunction "1_P$1") (pintype "passive"))
    )
    (net (code "37") (name "Net-(R16-2)") (class "Default")
      (node (ref "Q1") (pin "G") (pinfunction "G_G") (pintype "passive"))
      (node (ref "R16") (pin "P$2") (pinfunction "2_P$2") (pintype "passive"))
      (node (ref "R17") (pin "P$1") (pinfunction "1_P$1") (pintype "passive"))
    )
    (net (code "38") (name "Net-(R18-2)") (class "Default")
      (node (ref "Q2") (pin "G") (pinfunction "G_G") (pintype "passive"))
      (node (ref "R18") (pin "P$2") (pinfunction "2_P$2") (pintype "passive"))
      (node (ref "R19") (pin "P$1") (pinfunction "1_P$1") (pintype "passive"))
    )
    (net (code "39") (name "Net-(R20-2)") (class "Default")
      (node (ref "Q3") (pin "G") (pinfunction "G_G") (pintype "passive"))
      (node (ref "R20") (pin "P$2") (pinfunction "2_P$2") (pintype "passive"))
      (node (ref "R21") (pin "P$1") (pinfunction "1_P$1") (pintype "passive"))
    )
    (net (code "40") (name "Net-(R27-1)") (class "Default")
      (node (ref "J-AN3") (pin "2") (pinfunction "2_2") (pintype "bidirectional"))
      (node (ref "R27") (pin "P$1") (pinfunction "1_P$1") (pintype "passive"))
      (node (ref "R28") (pin "P$2") (pinfunction "2_P$2") (pintype "passive"))
    )
    (net (code "41") (name "Net-(TP1-P$1)") (class "Default")
      (node (ref "IC1") (pin "A3") (pinfunction "A3_A3") (pintype "bidirectional"))
      (node (ref "TP1") (pin "1") (pinfunction "P$1_1") (pintype "bidirectional"))
    )
    (net (code "42") (name "Net-(TP1-P$2)") (class "Default")
      (node (ref "IC1") (pin "A4") (pinfunction "A4_A4") (pintype "bidirectional"))
      (node (ref "TP1") (pin "2") (pinfunction "P$2_2") (pintype "bidirectional"))
    )
    (net (code "43") (name "OP1") (class "Default")
      (node (ref "Q1") (pin "D") (pinfunction "D_D") (pintype "passive"))
      (node (ref "TB6") (pin "1") (pinfunction "1_1") (pintype "bidirectional"))
    )
    (net (code "44") (name "OP2") (class "Default")
      (node (ref "Q2") (pin "D") (pinfunction "D_D") (pintype "passive"))
      (node (ref "TB6") (pin "2") (pinfunction "2_2") (pintype "bidirectional"))
    )
    (net (code "45") (name "OP3") (class "Default")
      (node (ref "Q3") (pin "D") (pinfunction "D_D") (pintype "passive"))
      (node (ref "TB7") (pin "1") (pinfunction "1_1") (pintype "bidirectional"))
    )
    (net (code "46") (name "OUT1") (class "Default")
      (node (ref "IC1") (pin "48") (pinfunction "48_48") (pintype "bidirectional"))
      (node (ref "R13") (pin "P$1") (pinfunction "1_P$1") (pintype "passive"))
    )
    (net (code "47") (name "OUT2") (class "Default")
      (node (ref "IC1") (pin "49") (pinfunction "49_49") (pintype "bidirectional"))
      (node (ref "R14") (pin "P$1") (pinfunction "1_P$1") (pintype "passive"))
    )
    (net (code "48") (name "OUT3") (class "Default")
      (node (ref "IC1") (pin "50") (pinfunction "50_50") (pintype "bidirectional"))
      (node (ref "R15") (pin "P$1") (pinfunction "1_P$1") (pintype "passive"))
    )
    (net (code "49") (name "PTCANH") (class "Default")
      (node (ref "IC3") (pin "7") (pinfunction "CANH_7") (pintype "bidirectional"))
      (node (ref "J-LEAF") (pin "4") (pinfunction "4_4") (pintype "passive"))
      (node (ref "R8") (pin "P$2") (pinfunction "2_P$2") (pintype "passive"))
    )
    (net (code "50") (name "PTCANL") (class "Default")
      (node (ref "IC3") (pin "6") (pinfunction "CANL_6") (pintype "bidirectional"))
      (node (ref "J-LEAF") (pin "5") (pinfunction "5_5") (pintype "passive"))
      (node (ref "R7") (pin "P$2") (pinfunction "2_P$2") (pintype "passive"))
    )
    (net (code "51") (name "RX2") (class "Default")
      (node (ref "ESP8266") (pin "7") (pinfunction "7_7") (pintype "bidirectional"))
      (node (ref "IC1") (pin "RX2") (pinfunction "RX2_RX2") (pintype "bidirectional"))
    )
    (net (code "52") (name "SCK") (class "Default")
      (node (ref "IC1") (pin "SCK_ICSP") (pinfunction "SCK_ICSP_SCK_ICSP") (pintype "bidirectional"))
      (node (ref "IC8") (pin "6") (pinfunction "P$6_6") (pintype "bidirectional"))
    )
    (net (code "53") (name "SCL") (class "Default")
      (node (ref "IC1") (pin "SCL") (pinfunction "SCL_SCL") (pintype "bidirectional"))
      (node (ref "IC7") (pin "6") (pinfunction "SCL_6") (pintype "input"))
      (node (ref "LCD") (pin "4") (pinfunction "4_4") (pintype "passive"))
      (node (ref "R12") (pin "P$1") (pinfunction "1_P$1") (pintype "passive"))
    )
    (net (code "54") (name "SDA") (class "Default")
      (node (ref "IC1") (pin "SDA") (pinfunction "SDA_SDA") (pintype "bidirectional"))
      (node (ref "IC7") (pin "5") (pinfunction "SDA_5") (pintype "bidirectional"))
      (node (ref "LCD") (pin "3") (pinfunction "3_3") (pintype "passive"))
      (node (ref "R11") (pin "P$1") (pinfunction "1_P$1") (pintype "passive"))
    )
    (net (code "55") (name "THROTTLE1") (class "Default")
      (node (ref "J-AN1") (pin "2") (pinfunction "2_2") (pintype "bidirectional"))
      (node (ref "R22") (pin "P$1") (pinfunction "1_P$1") (pintype "passive"))
    )
    (net (code "56") (name "THROTTLE2") (class "Default")
      (node (ref "J-AN2") (pin "2") (pinfunction "2_2") (pintype "bidirectional"))
      (node (ref "R24") (pin "P$1") (pinfunction "1_P$1") (pintype "passive"))
    )
    (net (code "57") (name "TX2") (class "Default")
      (node (ref "ESP8266") (pin "5") (pinfunction "5_5") (pintype "bidirectional"))
      (node (ref "IC1") (pin "TX2") (pinfunction "TX2_TX2") (pintype "bidirectional"))
    )
    (net (code "58") (name "unconnected-(ESP8266-Pad2)") (class "Default")
      (node (ref "ESP8266") (pin "2") (pinfunction "2_2") (pintype "bidirectional"))
    )
    (net (code "59") (name "unconnected-(ESP8266-Pad4)") (class "Default")
      (node (ref "ESP8266") (pin "4") (pinfunction "4_4") (pintype "bidirectional"))
    )
    (net (code "60") (name "unconnected-(ESP8266-Pad6)") (class "Default")
      (node (ref "ESP8266") (pin "6") (pinfunction "6_6") (pintype "bidirectional"))
    )
    (net (code "61") (name "unconnected-(ESP8266-Pad8)") (class "Default")
      (node (ref "ESP8266") (pin "8") (pinfunction "8_8") (pintype "bidirectional"))
    )
    (net (code "62") (name "unconnected-(ESP8266-Pad9)") (class "Default")
      (node (ref "ESP8266") (pin "9") (pinfunction "9_9") (pintype "bidirectional"))
    )
    (net (code "63") (name "unconnected-(ESP8266-Pad10)") (class "Default")
      (node (ref "ESP8266") (pin "10") (pinfunction "10_10") (pintype "bidirectional"))
    )
    (net (code "64") (name "unconnected-(IC1-Pad3)") (class "Default")
      (node (ref "IC1") (pin "3") (pinfunction "3_3") (pintype "bidirectional"))
    )
    (net (code "65") (name "unconnected-(IC1-Pad4)") (class "Default")
      (node (ref "IC1") (pin "4") (pinfunction "4_4") (pintype "bidirectional"))
    )
    (net (code "66") (name "unconnected-(IC1-Pad5V)") (class "Default")
      (node (ref "IC1") (pin "5V") (pinfunction "5V_5V") (pintype "bidirectional"))
    )
    (net (code "67") (name "unconnected-(IC1-Pad5V_A)") (class "Default")
      (node (ref "IC1") (pin "5V_A") (pinfunction "5V_A_5V_A") (pintype "bidirectional"))
    )
    (net (code "68") (name "unconnected-(IC1-Pad5V_B)") (class "Default")
      (node (ref "IC1") (pin "5V_B") (pinfunction "5V_B_5V_B") (pintype "bidirectional"))
    )
    (net (code "69") (name "unconnected-(IC1-Pad8)") (class "Default")
      (node (ref "IC1") (pin "8") (pinfunction "8_8") (pintype "bidirectional"))
    )
    (net (code "70") (name "unconnected-(IC1-Pad9)") (class "Default")
      (node (ref "IC1") (pin "9") (pinfunction "9_9") (pintype "bidirectional"))
    )
    (net (code "71") (name "unconnected-(IC1-Pad10)") (class "Default")
      (node (ref "IC1") (pin "10") (pinfunction "10_10") (pintype "bidirectional"))
    )
    (net (code "72") (name "unconnected-(IC1-Pad11)") (class "Default")
      (node (ref "IC1") (pin "11") (pinfunction "11_11") (pintype "bidirectional"))
    )
    (net (code "73") (name "unconnected-(IC1-Pad12)") (class "Default")
      (node (ref "IC1") (pin "12") (pinfunction "12_12") (pintype "bidirectional"))
    )
    (net (code "74") (name "unconnected-(IC1-Pad13)") (class "Default")
      (node (ref "IC1") (pin "13") (pinfunction "13_13") (pintype "bidirectional"))
    )
    (net (code "75") (name "unconnected-(IC1-Pad22)") (class "Default")
      (node (ref "IC1") (pin "22") (pinfunction "22_22") (pintype "bidirectional"))
    )
    (net (code "76") (name "unconnected-(IC1-Pad23)") (class "Default")
      (node (ref "IC1") (pin "23") (pinfunction "23_23") (pintype "bidirectional"))
    )
    (net (code "77") (name "unconnected-(IC1-Pad24)") (class "Default")
      (node (ref "IC1") (pin "24") (pinfunction "24_24") (pintype "bidirectional"))
    )
    (net (code "78") (name "unconnected-(IC1-Pad25)") (class "Default")
      (node (ref "IC1") (pin "25") (pinfunction "25_25") (pintype "bidirectional"))
    )
    (net (code "79") (name "unconnected-(IC1-Pad26)") (class "Default")
      (node (ref "IC1") (pin "26") (pinfunction "26_26") (pintype "bidirectional"))
    )
    (net (code "80") (name "unconnected-(IC1-Pad27)") (class "Default")
      (node (ref "IC1") (pin "27") (pinfunction "27_27") (pintype "bidirectional"))
    )
    (net (code "81") (name "unconnected-(IC1-Pad28)") (class "Default")
      (node (ref "IC1") (pin "28") (pinfunction "28_28") (pintype "bidirectional"))
    )
    (net (code "82") (name "unconnected-(IC1-Pad29)") (class "Default")
      (node (ref "IC1") (pin "29") (pinfunction "29_29") (pintype "bidirectional"))
    )
    (net (code "83") (name "unconnected-(IC1-Pad30)") (class "Default")
      (node (ref "IC1") (pin "30") (pinfunction "30_30") (pintype "bidirectional"))
    )
    (net (code "84") (name "unconnected-(IC1-Pad31)") (class "Default")
      (node (ref "IC1") (pin "31") (pinfunction "31_31") (pintype "bidirectional"))
    )
    (net (code "85") (name "unconnected-(IC1-Pad32)") (class "Default")
      (node (ref "IC1") (pin "32") (pinfunction "32_32") (pintype "bidirectional"))
    )
    (net (code "86") (name "unconnected-(IC1-Pad33)") (class "Default")
      (node (ref "IC1") (pin "33") (pinfunction "33_33") (pintype "bidirectional"))
    )
    (net (code "87") (name "unconnected-(IC1-Pad34)") (class "Default")
      (node (ref "IC1") (pin "34") (pinfunction "34_34") (pintype "bidirectional"))
    )
    (net (code "88") (name "unconnected-(IC1-Pad35)") (class "Default")
      (node (ref "IC1") (pin "35") (pinfunction "35_35") (pintype "bidirectional"))
    )
    (net (code "89") (name "unconnected-(IC1-Pad36)") (class "Default")
      (node (ref "IC1") (pin "36") (pinfunction "36_36") (pintype "bidirectional"))
    )
    (net (code "90") (name "unconnected-(IC1-Pad37)") (class "Default")
      (node (ref "IC1") (pin "37") (pinfunction "37_37") (pintype "bidirectional"))
    )
    (net (code "91") (name "unconnected-(IC1-Pad38)") (class "Default")
      (node (ref "IC1") (pin "38") (pinfunction "38_38") (pintype "bidirectional"))
    )
    (net (code "92") (name "unconnected-(IC1-Pad39)") (class "Default")
      (node (ref "IC1") (pin "39") (pinfunction "39_39") (pintype "bidirectional"))
    )
    (net (code "93") (name "unconnected-(IC1-Pad40)") (class "Default")
      (node (ref "IC1") (pin "40") (pinfunction "40_40") (pintype "bidirectional"))
    )
    (net (code "94") (name "unconnected-(IC1-Pad41)") (class "Default")
      (node (ref "IC1") (pin "41") (pinfunction "41_41") (pintype "bidirectional"))
    )
    (net (code "95") (name "unconnected-(IC1-Pad42)") (class "Default")
      (node (ref "IC1") (pin "42") (pinfunction "42_42") (pintype "bidirectional"))
    )
    (net (code "96") (name "unconnected-(IC1-Pad43)") (class "Default")
      (node (ref "IC1") (pin "43") (pinfunction "43_43") (pintype "bidirectional"))
    )
    (net (code "97") (name "unconnected-(IC1-Pad44)") (class "Default")
      (node (ref "IC1") (pin "44") (pinfunction "44_44") (pintype "bidirectional"))
    )
    (net (code "98") (name "unconnected-(IC1-Pad45)") (class "Default")
      (node (ref "IC1") (pin "45") (pinfunction "45_45") (pintype "bidirectional"))
    )
    (net (code "99") (name "unconnected-(IC1-Pad46)") (class "Default")
      (node (ref "IC1") (pin "46") (pinfunction "46_46") (pintype "bidirectional"))
    )
    (net (code "100") (name "unconnected-(IC1-Pad47)") (class "Default")
      (node (ref "IC1") (pin "47") (pinfunction "47_47") (pintype "bidirectional"))
    )
    (net (code "101") (name "unconnected-(IC1-Pad51)") (class "Default")
      (node (ref "IC1") (pin "51") (pinfunction "51_51") (pintype "bidirectional"))
    )
    (net (code "102") (name "unconnected-(IC1-Pad52)") (class "Default")
      (node (ref "IC1") (pin "52") (pinfunction "52_52") (pintype "bidirectional"))
    )
    (net (code "103") (name "unconnected-(IC1-PadA5)") (class "Default")
      (node (ref "IC1") (pin "A5") (pinfunction "A5_A5") (pintype "bidirectional"))
    )
    (net (code "104") (name "unconnected-(IC1-PadA6)") (class "Default")
      (node (ref "IC1") (pin "A6") (pinfunction "A6_A6") (pintype "bidirectional"))
    )
    (net (code "105") (name "unconnected-(IC1-PadA8)") (class "Default")
      (node (ref "IC1") (pin "A8") (pinfunction "A8_A8") (pintype "bidirectional"))
    )
    (net (code "106") (name "unconnected-(IC1-PadA9)") (class "Default")
      (node (ref "IC1") (pin "A9") (pinfunction "A9_A9") (pintype "bidirectional"))
    )
    (net (code "107") (name "unconnected-(IC1-PadA10)") (class "Default")
      (node (ref "IC1") (pin "A10") (pinfunction "A10_A10") (pintype "bidirectional"))
    )
    (net (code "108") (name "unconnected-(IC1-PadA11)") (class "Default")
      (node (ref "IC1") (pin "A11") (pinfunction "A11_A11") (pintype "bidirectional"))
    )
    (net (code "109") (name "unconnected-(IC1-PadAREF)") (class "Default")
      (node (ref "IC1") (pin "AREF") (pinfunction "AREF_AREF") (pintype "bidirectional"))
    )
    (net (code "110") (name "unconnected-(IC1-PadDAC1)") (class "Default")
      (node (ref "IC1") (pin "DAC1") (pinfunction "DAC1_DAC1") (pintype "bidirectional"))
    )
    (net (code "111") (name "unconnected-(IC1-PadGND_DEBUG)") (class "Default")
      (node (ref "IC1") (pin "GND_DEBUG") (pinfunction "GND_DEBUG_GND_DEBUG") (pintype "bidirectional"))
    )
    (net (code "112") (name "unconnected-(IC1-PadGND_ICSP)") (class "Default")
      (node (ref "IC1") (pin "GND_ICSP") (pinfunction "GND_ICSP_GND_ICSP") (pintype "bidirectional"))
    )
    (net (code "113") (name "unconnected-(IC1-PadIOREF)") (class "Default")
      (node (ref "IC1") (pin "IOREF") (pinfunction "IOREF_IOREF") (pintype "bidirectional"))
    )
    (net (code "114") (name "unconnected-(IC1-PadNC)") (class "Default")
      (node (ref "IC1") (pin "NC") (pinfunction "NC_NC") (pintype "bidirectional"))
    )
    (net (code "115") (name "unconnected-(IC1-PadRESET)") (class "Default")
      (node (ref "IC1") (pin "RESET") (pinfunction "RESET_RESET") (pintype "bidirectional"))
    )
    (net (code "116") (name "unconnected-(IC1-PadRESET_DEBUG)") (class "Default")
      (node (ref "IC1") (pin "RESET_DEBUG") (pinfunction "RESET_DEBUG_RESET_DEBUG") (pintype "bidirectional"))
    )
    (net (code "117") (name "unconnected-(IC1-PadRESET_ICSP)") (class "Default")
      (node (ref "IC1") (pin "RESET_ICSP") (pinfunction "RESET_ICSP_RESET_ICSP") (pintype "bidirectional"))
    )
    (net (code "118") (name "unconnected-(IC1-PadRX0)") (class "Default")
      (node (ref "IC1") (pin "RX0") (pinfunction "RX0_RX0") (pintype "bidirectional"))
    )
    (net (code "119") (name "unconnected-(IC1-PadRX1)") (class "Default")
      (node (ref "IC1") (pin "RX1") (pinfunction "RX1_RX1") (pintype "bidirectional"))
    )
    (net (code "120") (name "unconnected-(IC1-PadRX3)") (class "Default")
      (node (ref "IC1") (pin "RX3") (pinfunction "RX3_RX3") (pintype "bidirectional"))
    )
    (net (code "121") (name "unconnected-(IC1-PadSCL1)") (class "Default")
      (node (ref "IC1") (pin "SCL1") (pinfunction "SCL1_SCL1") (pintype "bidirectional"))
    )
    (net (code "122") (name "unconnected-(IC1-PadSDA1)") (class "Default")
      (node (ref "IC1") (pin "SDA1") (pinfunction "SDA1_SDA1") (pintype "bidirectional"))
    )
    (net (code "123") (name "unconnected-(IC1-PadSWCLK_DEBUG)") (class "Default")
      (node (ref "IC1") (pin "SWCLK_DEBUG") (pinfunction "SWCLK_DEBUG_SWCLK_DEBUG") (pintype "bidirectional"))
    )
    (net (code "124") (name "unconnected-(IC1-PadSWDIO_DEBUG)") (class "Default")
      (node (ref "IC1") (pin "SWDIO_DEBUG") (pinfunction "SWDIO_DEBUG_SWDIO_DEBUG") (pintype "bidirectional"))
    )
    (net (code "125") (name "unconnected-(IC1-PadTX0)") (class "Default")
      (node (ref "IC1") (pin "TX0") (pinfunction "TX0_TX0") (pintype "bidirectional"))
    )
    (net (code "126") (name "unconnected-(IC1-PadTX1)") (class "Default")
      (node (ref "IC1") (pin "TX1") (pinfunction "TX1_TX1") (pintype "bidirectional"))
    )
    (net (code "127") (name "unconnected-(IC1-PadTX3)") (class "Default")
      (node (ref "IC1") (pin "TX3") (pinfunction "TX3_TX3") (pintype "bidirectional"))
    )
    (net (code "128") (name "unconnected-(IC8-P$3-Pad3)") (class "Default")
      (node (ref "IC8") (pin "3") (pinfunction "P$3_3") (pintype "bidirectional"))
    )
    (net (code "129") (name "unconnected-(IC8-P$7-Pad7)") (class "Default")
      (node (ref "IC8") (pin "7") (pinfunction "P$7_7") (pintype "bidirectional"))
    )
  )
)
